# STorM32_NT_imu_v11_mini-mpu9250.net
KiCad netlist of a schematic drawn in EAGLE
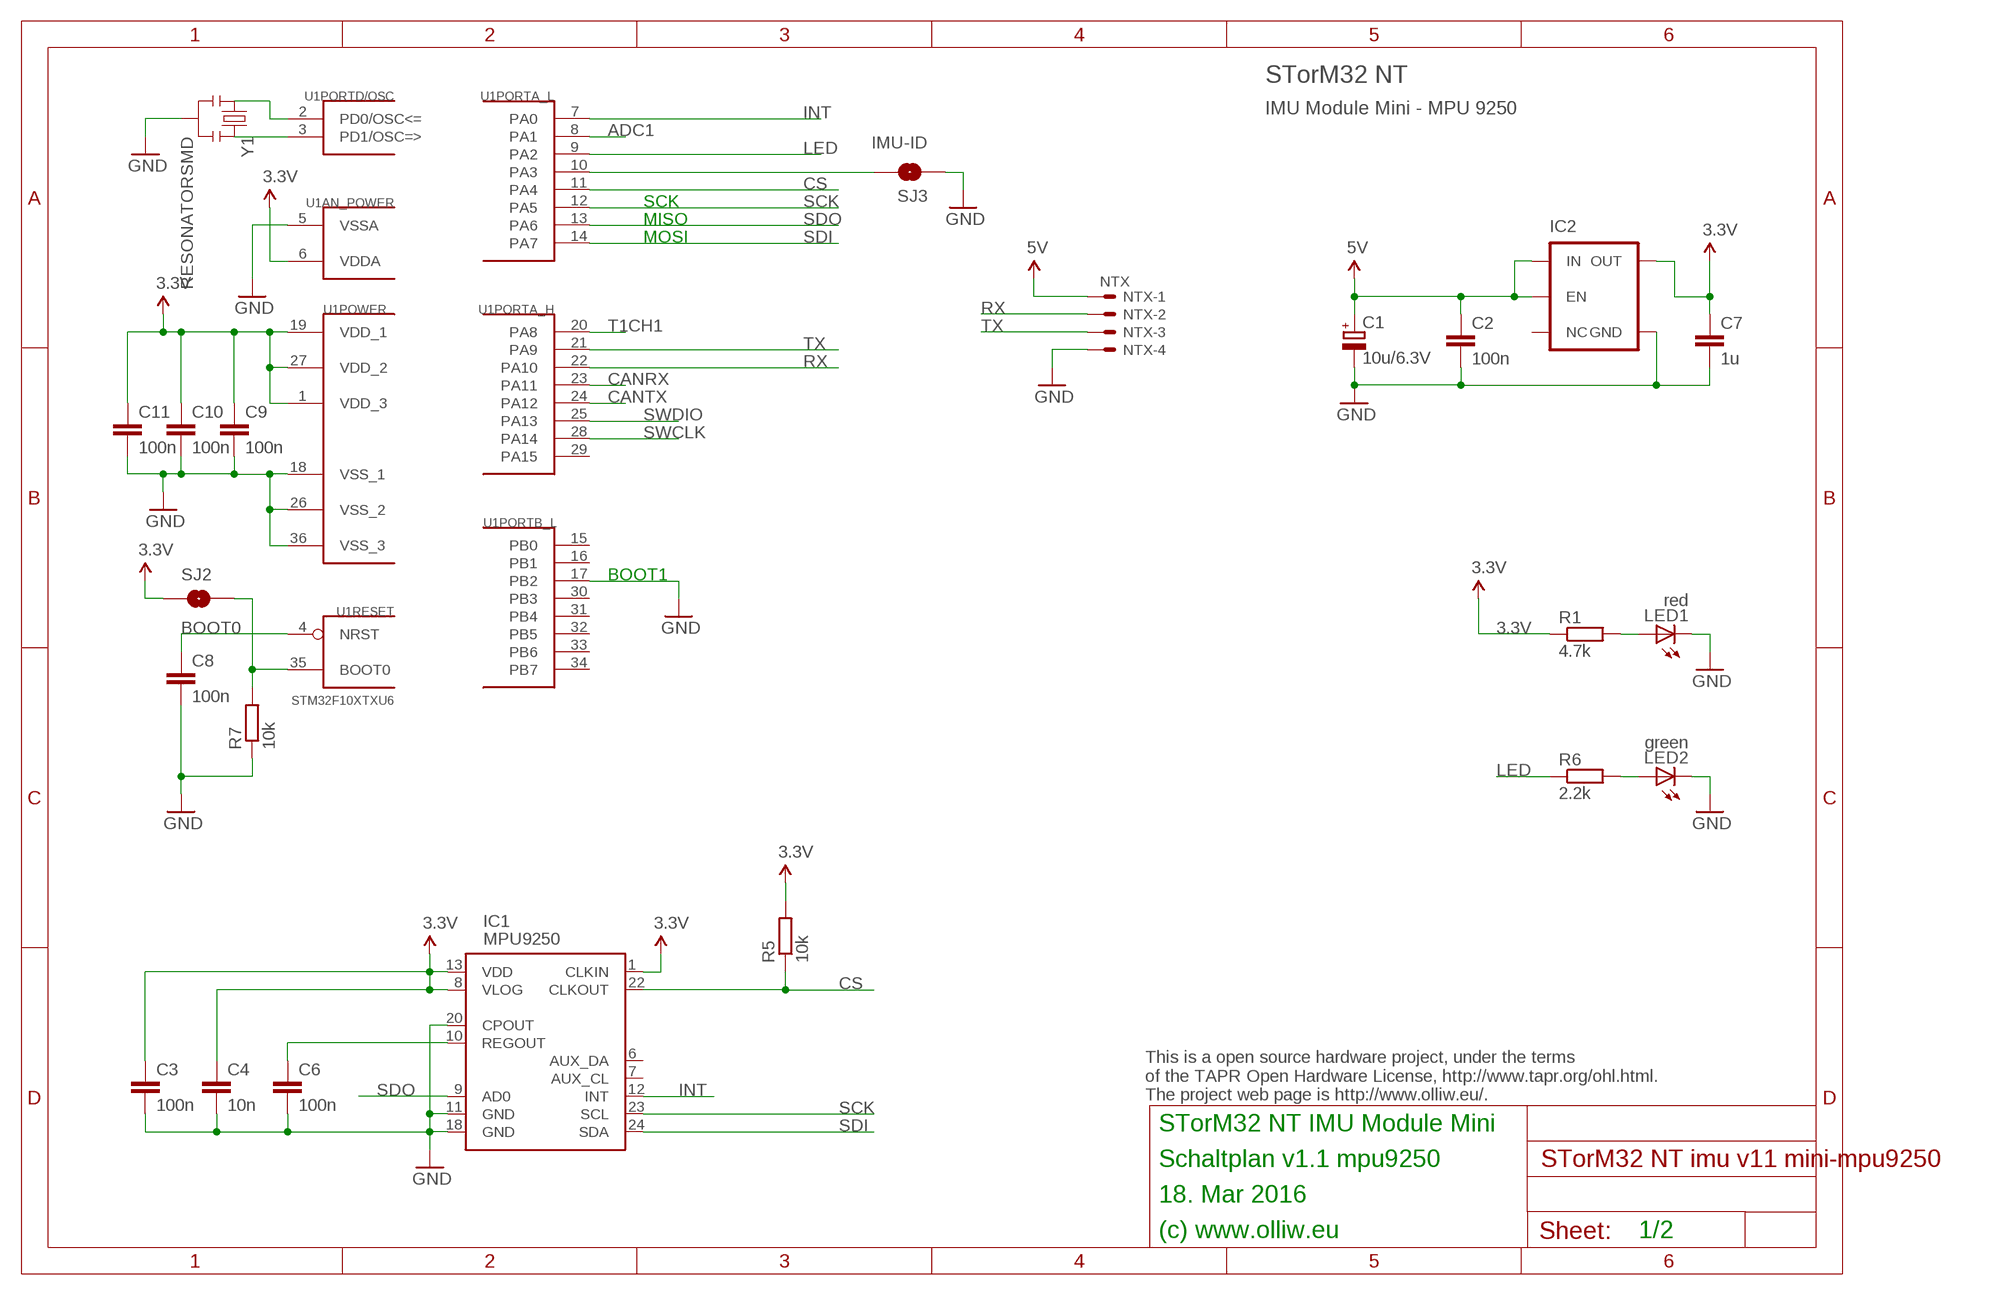
[diagram p0: schematic, sheet 1]

(export (version "E")
  (design (tool "Eeschema 10.0.6"))
  (components
    (comp (ref "C1")
      (value "10u/6.3V")
      (footprint "eagle-import:SMC_A")
      (libsource (lib "eagle-import") (part "CPOL-EUSMCA"))
    )
    (comp (ref "C2")
      (value "100n")
      (footprint "eagle-import:C0402")
      (libsource (lib "eagle-import") (part "C-EUC0402"))
    )
    (comp (ref "C3")
      (value "100n")
      (footprint "eagle-import:C0402")
      (libsource (lib "eagle-import") (part "C-EUC0402"))
    )
    (comp (ref "C4")
      (value "10n")
      (footprint "eagle-import:C0402")
      (libsource (lib "eagle-import") (part "C-EUC0402"))
    )
    (comp (ref "C6")
      (value "100n")
      (footprint "eagle-import:C0402")
      (libsource (lib "eagle-import") (part "C-EUC0402"))
    )
    (comp (ref "C7")
      (value "1u")
      (footprint "eagle-import:C0402")
      (libsource (lib "eagle-import") (part "C-EUC0402"))
    )
    (comp (ref "C8")
      (value "100n")
      (footprint "eagle-import:C0402")
      (libsource (lib "eagle-import") (part "C-EUC0402"))
    )
    (comp (ref "C9")
      (value "100n")
      (footprint "eagle-import:C0402")
      (libsource (lib "eagle-import") (part "C-EUC0402"))
    )
    (comp (ref "C10")
      (value "100n")
      (footprint "eagle-import:C0402")
      (libsource (lib "eagle-import") (part "C-EUC0402"))
    )
    (comp (ref "C11")
      (value "100n")
      (footprint "eagle-import:C0402")
      (libsource (lib "eagle-import") (part "C-EUC0402"))
    )
    (comp (ref "IC1")
      (value "MPU9250")
      (footprint "eagle-import:QFN-24-3X3")
      (libsource (lib "eagle-import") (part "IMU3000QFN-24-0.4MIL"))
    )
    (comp (ref "IC2")
      (value "V_REG_TPS76433SOT23-5")
      (footprint "eagle-import:SOT23-5")
      (libsource (lib "eagle-import") (part "V_REG_TPS76433SOT23-5"))
    )
    (comp (ref "LED1")
      (value "red")
      (footprint "eagle-import:CHIPLED_0603")
      (libsource (lib "eagle-import") (part "LEDCHIPLED_0603"))
    )
    (comp (ref "LED2")
      (value "green")
      (footprint "eagle-import:CHIPLED_0603")
      (libsource (lib "eagle-import") (part "LEDCHIPLED_0603"))
    )
    (comp (ref "NTX")
      (value "NTX")
      (footprint "eagle-import:SM04B-SRSS-TB")
      (libsource (lib "eagle-import") (part "?M04B-SRSS-TBS"))
    )
    (comp (ref "R1")
      (value "4.7k")
      (footprint "eagle-import:R0402")
      (libsource (lib "eagle-import") (part "R-EU_R0402"))
    )
    (comp (ref "R5")
      (value "10k")
      (footprint "eagle-import:R0402")
      (libsource (lib "eagle-import") (part "R-EU_R0402"))
    )
    (comp (ref "R6")
      (value "2.2k")
      (footprint "eagle-import:R0402")
      (libsource (lib "eagle-import") (part "R-EU_R0402"))
    )
    (comp (ref "R7")
      (value "10k")
      (footprint "eagle-import:R0402")
      (libsource (lib "eagle-import") (part "R-EU_R0402"))
    )
    (comp (ref "SJ2")
      (value "BOOT0")
      (footprint "eagle-import:SJ_2S-NO")
      (libsource (lib "eagle-import") (part "SOLDERJUMPERNO"))
    )
    (comp (ref "SJ3")
      (value "IMU-ID")
      (footprint "eagle-import:SJ_2S-NO")
      (libsource (lib "eagle-import") (part "SOLDERJUMPERNO"))
    )
    (comp (ref "U1")
      (value "STM32F10XTXU6")
      (footprint "eagle-import:VFQFPN36")
      (libsource (lib "eagle-import") (part "STM32F10XTXU6"))
    )
    (comp (ref "Y1")
      (value "RESONATORSMD")
      (footprint "eagle-import:RESONATOR-SMD")
      (libsource (lib "eagle-import") (part "RESONATORSMD"))
    )
  )
  (nets
    (net (code "1") (name "/ADC1") (class "Default")
      (node (ref "U1") (pin "8") (pinfunction "PA1_8") (pintype "bidirectional"))
    )
    (net (code "2") (name "/CANRX") (class "Default")
      (node (ref "U1") (pin "23") (pinfunction "PA11_23") (pintype "bidirectional"))
    )
    (net (code "3") (name "/CANTX") (class "Default")
      (node (ref "U1") (pin "24") (pinfunction "PA12_24") (pintype "bidirectional"))
    )
    (net (code "4") (name "/CS") (class "Default")
      (node (ref "IC1") (pin "22") (pinfunction "CLKOUT_22") (pintype "bidirectional"))
      (node (ref "R5") (pin "1") (pinfunction "1_1") (pintype "passive"))
      (node (ref "U1") (pin "11") (pinfunction "PA4_11") (pintype "bidirectional"))
    )
    (net (code "5") (name "/INT") (class "Default")
      (node (ref "IC1") (pin "12") (pinfunction "INT_12") (pintype "bidirectional"))
      (node (ref "U1") (pin "7") (pinfunction "PA0_7") (pintype "bidirectional"))
    )
    (net (code "6") (name "/LED") (class "Default")
      (node (ref "R6") (pin "1") (pinfunction "1_1") (pintype "passive"))
      (node (ref "U1") (pin "9") (pinfunction "PA2_9") (pintype "bidirectional"))
    )
    (net (code "7") (name "/RX") (class "Default")
      (node (ref "NTX") (pin "2") (pinfunction "S_2") (pintype "passive"))
      (node (ref "U1") (pin "22") (pinfunction "PA10_22") (pintype "bidirectional"))
    )
    (net (code "8") (name "/SCK") (class "Default")
      (node (ref "IC1") (pin "23") (pinfunction "SCL_23") (pintype "bidirectional"))
      (node (ref "U1") (pin "12") (pinfunction "PA5_12") (pintype "bidirectional"))
    )
    (net (code "9") (name "/SDI") (class "Default")
      (node (ref "IC1") (pin "24") (pinfunction "SDA_24") (pintype "bidirectional"))
      (node (ref "U1") (pin "14") (pinfunction "PA7_14") (pintype "bidirectional"))
    )
    (net (code "10") (name "/SDO") (class "Default")
      (node (ref "IC1") (pin "9") (pinfunction "AD0_9") (pintype "bidirectional"))
      (node (ref "U1") (pin "13") (pinfunction "PA6_13") (pintype "bidirectional"))
    )
    (net (code "11") (name "/SWCLK") (class "Default")
      (node (ref "U1") (pin "28") (pinfunction "PA14_28") (pintype "bidirectional"))
    )
    (net (code "12") (name "/SWDIO") (class "Default")
      (node (ref "U1") (pin "25") (pinfunction "PA13_25") (pintype "bidirectional"))
    )
    (net (code "13") (name "/T1CH1") (class "Default")
      (node (ref "U1") (pin "20") (pinfunction "PA8_20") (pintype "bidirectional"))
    )
    (net (code "14") (name "/TX") (class "Default")
      (node (ref "NTX") (pin "3") (pinfunction "S_3") (pintype "passive"))
      (node (ref "U1") (pin "21") (pinfunction "PA9_21") (pintype "bidirectional"))
    )
    (net (code "15") (name "3.3V") (class "Default")
      (node (ref "C10") (pin "1") (pinfunction "1_1") (pintype "passive"))
      (node (ref "C11") (pin "1") (pinfunction "1_1") (pintype "passive"))
      (node (ref "C3") (pin "1") (pinfunction "1_1") (pintype "passive"))
      (node (ref "C4") (pin "1") (pinfunction "1_1") (pintype "passive"))
      (node (ref "C7") (pin "1") (pinfunction "1_1") (pintype "passive"))
      (node (ref "C9") (pin "1") (pinfunction "1_1") (pintype "passive"))
      (node (ref "IC1") (pin "1") (pinfunction "CLKIN_1") (pintype "bidirectional"))
      (node (ref "IC1") (pin "13") (pinfunction "VDD_13") (pintype "bidirectional"))
      (node (ref "IC1") (pin "8") (pinfunction "VLOG_8") (pintype "bidirectional"))
      (node (ref "IC2") (pin "5") (pinfunction "OUT_5") (pintype "passive"))
      (node (ref "R1") (pin "1") (pinfunction "1_1") (pintype "passive"))
      (node (ref "R5") (pin "2") (pinfunction "2_2") (pintype "passive"))
      (node (ref "SJ2") (pin "1") (pinfunction "1_1") (pintype "passive"))
      (node (ref "U1") (pin "1") (pinfunction "VDD_3_1") (pintype "power_in"))
      (node (ref "U1") (pin "19") (pinfunction "VDD_1_19") (pintype "power_in"))
      (node (ref "U1") (pin "27") (pinfunction "VDD_2_27") (pintype "power_in"))
      (node (ref "U1") (pin "6") (pinfunction "VDDA_6") (pintype "power_in"))
    )
    (net (code "16") (name "5V") (class "Default")
      (node (ref "C1") (pin "+") (pinfunction "+_+") (pintype "passive"))
      (node (ref "C2") (pin "1") (pinfunction "1_1") (pintype "passive"))
      (node (ref "IC2") (pin "1") (pinfunction "IN_1") (pintype "input"))
      (node (ref "IC2") (pin "3") (pinfunction "EN_3") (pintype "input"))
      (node (ref "NTX") (pin "1") (pinfunction "S_1") (pintype "passive"))
    )
    (net (code "17") (name "GND") (class "Default")
      (node (ref "C1") (pin "-") (pinfunction "-_-") (pintype "passive"))
      (node (ref "C10") (pin "2") (pinfunction "2_2") (pintype "passive"))
      (node (ref "C11") (pin "2") (pinfunction "2_2") (pintype "passive"))
      (node (ref "C2") (pin "2") (pinfunction "2_2") (pintype "passive"))
      (node (ref "C3") (pin "2") (pinfunction "2_2") (pintype "passive"))
      (node (ref "C4") (pin "2") (pinfunction "2_2") (pintype "passive"))
      (node (ref "C6") (pin "2") (pinfunction "2_2") (pintype "passive"))
      (node (ref "C7") (pin "2") (pinfunction "2_2") (pintype "passive"))
      (node (ref "C8") (pin "2") (pinfunction "2_2") (pintype "passive"))
      (node (ref "C9") (pin "2") (pinfunction "2_2") (pintype "passive"))
      (node (ref "IC1") (pin "11") (pinfunction "GND_11") (pintype "bidirectional"))
      (node (ref "IC1") (pin "18") (pinfunction "GND_18") (pintype "bidirectional"))
      (node (ref "IC1") (pin "20") (pinfunction "CPOUT_20") (pintype "bidirectional"))
      (node (ref "IC2") (pin "2") (pinfunction "GND_2") (pintype "input"))
      (node (ref "LED1") (pin "C") (pinfunction "C_C") (pintype "passive"))
      (node (ref "LED2") (pin "C") (pinfunction "C_C") (pintype "passive"))
      (node (ref "NTX") (pin "4") (pinfunction "S_4") (pintype "passive"))
      (node (ref "R7") (pin "1") (pinfunction "1_1") (pintype "passive"))
      (node (ref "SJ3") (pin "1") (pinfunction "1_1") (pintype "passive"))
      (node (ref "U1") (pin "17") (pinfunction "PB2_17") (pintype "bidirectional"))
      (node (ref "U1") (pin "18") (pinfunction "VSS_1_18") (pintype "power_in"))
      (node (ref "U1") (pin "26") (pinfunction "VSS_2_26") (pintype "power_in"))
      (node (ref "U1") (pin "36") (pinfunction "VSS_3_36") (pintype "power_in"))
      (node (ref "U1") (pin "5") (pinfunction "VSSA_5") (pintype "power_in"))
      (node (ref "Y1") (pin "2") (pinfunction "2_2") (pintype "passive"))
    )
    (net (code "18") (name "Net-(IC1-REGOUT)") (class "Default")
      (node (ref "C6") (pin "1") (pinfunction "1_1") (pintype "passive"))
      (node (ref "IC1") (pin "10") (pinfunction "REGOUT_10") (pintype "bidirectional"))
    )
    (net (code "19") (name "Net-(LED1-PadA)") (class "Default")
      (node (ref "LED1") (pin "A") (pinfunction "A_A") (pintype "passive"))
      (node (ref "R1") (pin "2") (pinfunction "2_2") (pintype "passive"))
    )
    (net (code "20") (name "Net-(LED2-PadA)") (class "Default")
      (node (ref "LED2") (pin "A") (pinfunction "A_A") (pintype "passive"))
      (node (ref "R6") (pin "2") (pinfunction "2_2") (pintype "passive"))
    )
    (net (code "21") (name "Net-(U1C-PA3)") (class "Default")
      (node (ref "SJ3") (pin "2") (pinfunction "2_2") (pintype "passive"))
      (node (ref "U1") (pin "10") (pinfunction "PA3_10") (pintype "bidirectional"))
    )
    (net (code "22") (name "Net-(U1E-PD0{slash}OSC<=)") (class "Default")
      (node (ref "U1") (pin "2") (pinfunction "PD0/OSC<=_2") (pintype "bidirectional"))
      (node (ref "Y1") (pin "1") (pinfunction "1_1") (pintype "passive"))
    )
    (net (code "23") (name "Net-(U1E-PD1{slash}OSC=>)") (class "Default")
      (node (ref "U1") (pin "3") (pinfunction "PD1/OSC=>_3") (pintype "bidirectional"))
      (node (ref "Y1") (pin "3") (pinfunction "3_3") (pintype "passive"))
    )
    (net (code "24") (name "Net-(U1G-BOOT0)") (class "Default")
      (node (ref "R7") (pin "2") (pinfunction "2_2") (pintype "passive"))
      (node (ref "SJ2") (pin "2") (pinfunction "2_2") (pintype "passive"))
      (node (ref "U1") (pin "35") (pinfunction "BOOT0_35") (pintype "input"))
    )
    (net (code "25") (name "Net-(U1G-NRST)") (class "Default")
      (node (ref "C8") (pin "1") (pinfunction "1_1") (pintype "passive"))
      (node (ref "U1") (pin "4") (pinfunction "NRST_4") (pintype "input"))
    )
    (net (code "26") (name "unconnected-(IC1-AUX_CL-Pad7)") (class "Default")
      (node (ref "IC1") (pin "7") (pinfunction "AUX_CL_7") (pintype "bidirectional"))
    )
    (net (code "27") (name "unconnected-(IC1-AUX_DA-Pad6)") (class "Default")
      (node (ref "IC1") (pin "6") (pinfunction "AUX_DA_6") (pintype "bidirectional"))
    )
    (net (code "28") (name "unconnected-(IC2-NC-Pad4)") (class "Default")
      (node (ref "IC2") (pin "4") (pinfunction "NC_4") (pintype "input"))
    )
    (net (code "29") (name "unconnected-(U1B-PA15-Pad29)") (class "Default")
      (node (ref "U1") (pin "29") (pinfunction "PA15_29") (pintype "bidirectional"))
    )
    (net (code "30") (name "unconnected-(U1D-PB0-Pad15)") (class "Default")
      (node (ref "U1") (pin "15") (pinfunction "PB0_15") (pintype "bidirectional"))
    )
    (net (code "31") (name "unconnected-(U1D-PB1-Pad16)") (class "Default")
      (node (ref "U1") (pin "16") (pinfunction "PB1_16") (pintype "bidirectional"))
    )
    (net (code "32") (name "unconnected-(U1D-PB3-Pad30)") (class "Default")
      (node (ref "U1") (pin "30") (pinfunction "PB3_30") (pintype "bidirectional"))
    )
    (net (code "33") (name "unconnected-(U1D-PB4-Pad31)") (class "Default")
      (node (ref "U1") (pin "31") (pinfunction "PB4_31") (pintype "bidirectional"))
    )
    (net (code "34") (name "unconnected-(U1D-PB5-Pad32)") (class "Default")
      (node (ref "U1") (pin "32") (pinfunction "PB5_32") (pintype "bidirectional"))
    )
    (net (code "35") (name "unconnected-(U1D-PB6-Pad33)") (class "Default")
      (node (ref "U1") (pin "33") (pinfunction "PB6_33") (pintype "bidirectional"))
    )
    (net (code "36") (name "unconnected-(U1D-PB7-Pad34)") (class "Default")
      (node (ref "U1") (pin "34") (pinfunction "PB7_34") (pintype "bidirectional"))
    )
  )
)
